# MB1137.net
KiCad netlist of a schematic drawn in Altium Designer
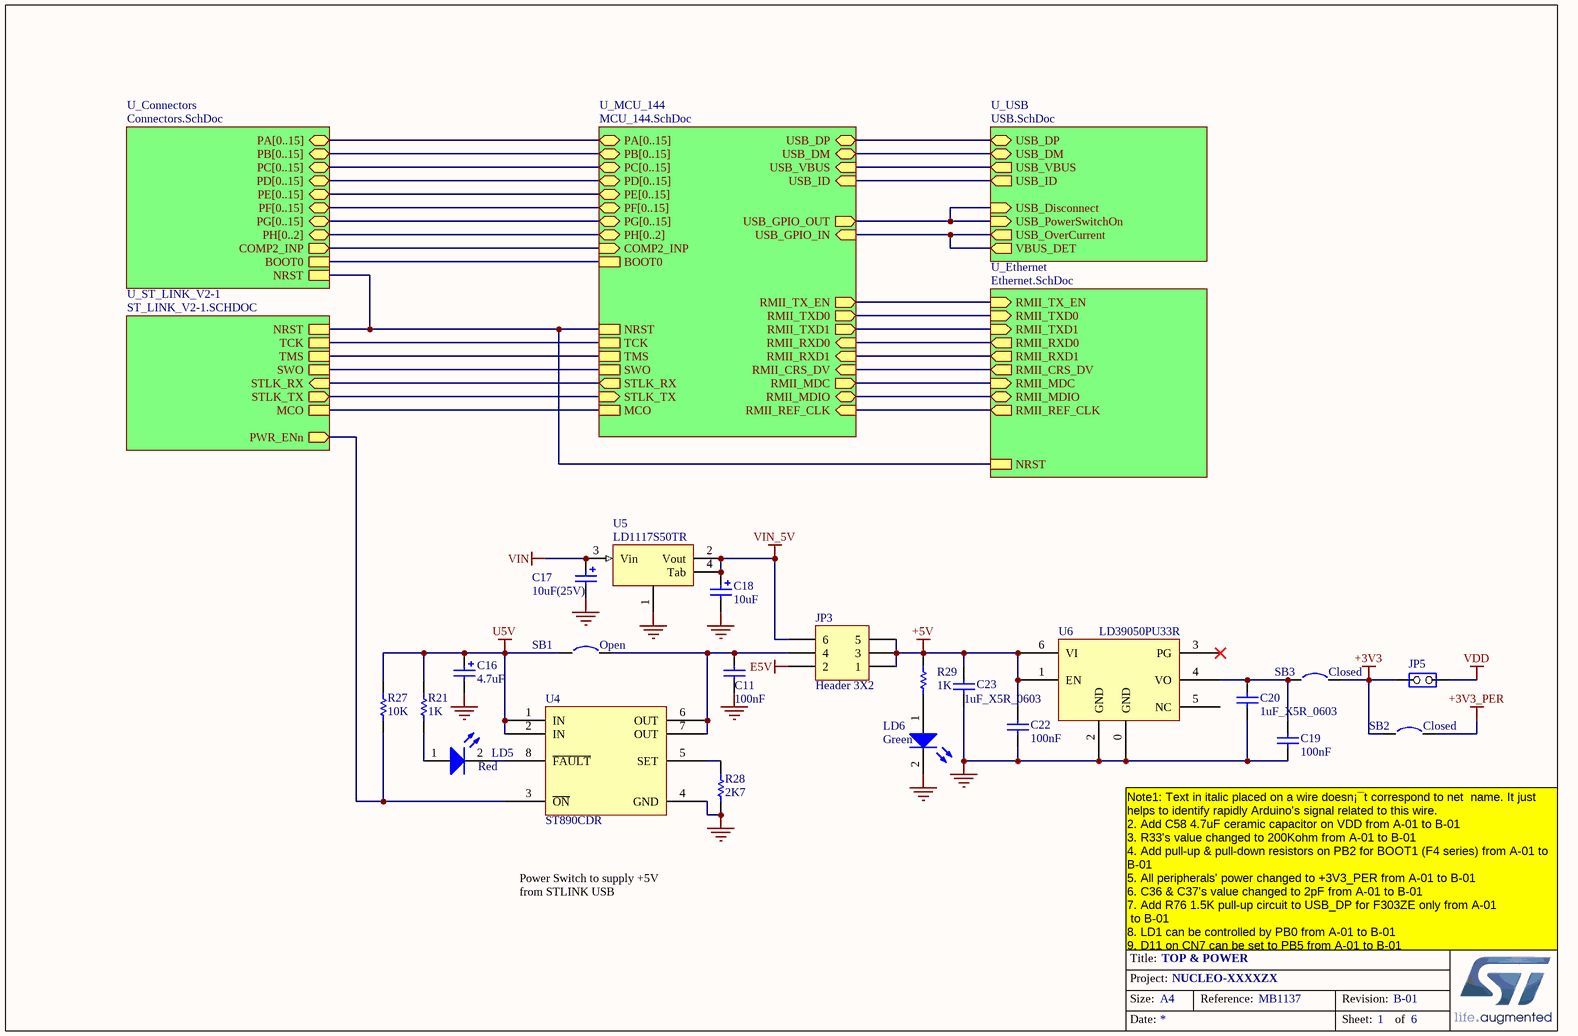
[diagram p0: MB1137.SchDoc]

(export (version "E")
  (design (tool "Eeschema 10.0.6"))
  (components
    (comp (ref "C11")
      (value "100nF")
      (footprint "0603C")
      (description "Capacitor 0402 / 0603 / 0805")
      (libsource (lib "MCD_TOOLS") (part "Capacitor_ST"))
    )
    (comp (ref "C16")
      (value "4.7uF")
      (footprint "TAN-A")
      (description "Polarized Capacitor (Radial)")
      (fields (field (name "PUBLISHER") "Altium Limited"))
      (libsource (lib "*") (part "Cap Pol1"))
    )
    (comp (ref "C17")
      (value "10uF(25V)")
      (footprint "TAN-B")
      (description "Polarized Capacitor (Radial)")
      (fields (field (name "PUBLISHER") "Altium Limited"))
      (libsource (lib "Miscellaneous Devices") (part "Cap Pol1"))
    )
    (comp (ref "C18")
      (value "10uF")
      (footprint "TAN-A")
      (description "Polarized Capacitor (Radial)")
      (fields (field (name "PUBLISHER") "Altium Limited"))
      (libsource (lib "Miscellaneous Devices") (part "Cap Pol1"))
    )
    (comp (ref "C19")
      (value "100nF")
      (footprint "0603C")
      (description "Capacitor 0402 / 0603 / 0805")
      (libsource (lib "MCD_TOOLS") (part "Capacitor_ST"))
    )
    (comp (ref "C20")
      (value "1uF_X5R_0603")
      (footprint "0603C")
      (description "0603  X5R 1µF")
      (fields (field (name "TOLERANCE") "10%"))
      (libsource (lib "MB963_1") (part "CAP SMD 0603  X5R 1µF 25V 10%"))
    )
    (comp (ref "C22")
      (value "100nF")
      (footprint "0603C")
      (description "Capacitor 0402 / 0603 / 0805")
      (libsource (lib "MCD_TOOLS") (part "Capacitor_ST"))
    )
    (comp (ref "C23")
      (value "1uF_X5R_0603")
      (footprint "0603C")
      (description "0603  X5R 1µF")
      (fields (field (name "TOLERANCE") "10%"))
      (libsource (lib "MB963_1") (part "CAP SMD 0603  X5R 1µF 25V 10%"))
    )
    (comp (ref "JP3")
      (value "Header 3X2")
      (footprint "HDR_3x2_2R54_V_M")
      (description "Header, 3-Pin, Dual row")
      (fields (field (name "PUBLISHER") "Altium Limited"))
      (libsource (lib "Miscellaneous Connectors") (part "Header 3X2"))
    )
    (comp (ref "JP5") (value "~") (footprint "HDR_1x2_2R54_V_M_S") (libsource (lib "*") (part "JP2")))
    (comp (ref "LD5")
      (value "Red")
      (footprint "0603D-R")
      (description "Typical RED, GREEN, YELLOW, AMBER GaAs LED")
      (fields (field (name "PUBLISHER") "Altium Limited"))
      (libsource (lib "Miscellaneous Devices") (part "LED2"))
    )
    (comp (ref "LD6")
      (value "Green")
      (footprint "0603D-G")
      (description "Typical RED, GREEN, YELLOW, AMBER GaAs LED")
      (fields (field (name "PUBLISHER") "Altium Limited"))
      (libsource (lib "") (part "LED2_1"))
    )
    (comp (ref "R21")
      (value "1K")
      (footprint "0603R")
      (description "Resistor")
      (fields (field (name "PUBLISHER") "Altium Limited"))
      (libsource (lib "*") (part "Res1"))
    )
    (comp (ref "R27")
      (value "10K")
      (footprint "STM-SMEE:0603R")
      (description "Resistor 0402 or 0603 or 0805")
      (libsource (lib "MCD_TOOLS") (part "Resistor_ST"))
    )
    (comp (ref "R28")
      (value "2K7")
      (footprint "STM-SMEE:0603R")
      (description "Resistor 0402 or 0603 or 0805")
      (libsource (lib "MCD_TOOLS") (part "Resistor_ST"))
    )
    (comp (ref "R29")
      (value "1K")
      (footprint "0603R")
      (description "Resistor 0402 or 0603 or 0805")
      (libsource (lib "MCD_TOOLS") (part "Resistor_ST"))
    )
    (comp (ref "SB1")
      (value "Open")
      (footprint "SB_0603")
      (description "Circuit Breaker")
      (fields (field (name "PUBLISHER") "Altium Limited"))
      (libsource (lib "MB1167") (part "Circuit Breaker"))
    )
    (comp (ref "SB2")
      (value "Closed")
      (footprint "SB_0603")
      (description "Circuit Breaker")
      (fields (field (name "PUBLISHER") "Altium Limited"))
      (libsource (lib "MB1167") (part "Circuit Breaker_close"))
    )
    (comp (ref "SB3")
      (value "Closed")
      (footprint "SB_0603")
      (description "Circuit Breaker")
      (fields (field (name "PUBLISHER") "Altium Limited"))
      (libsource (lib "MB1167") (part "Circuit Breaker_close"))
    )
    (comp (ref "U4")
      (value "ST890CDR")
      (footprint "SOIC8_1R27_4R9X6")
      (libsource (lib "MB1137") (part "ST890CDR"))
    )
    (comp (ref "U5") (value "LD1117S50TR") (footprint "SOT-223") (libsource (lib "MB1137") (part "LD1117")))
    (comp (ref "U6")
      (value "LD39050PU33R")
      (footprint "DFN6_0R95_3x3_TP")
      (libsource (lib "MB1137") (part "LD39050P"))
    )
  )
  (nets
    (net (code "1") (name "+3V3") (class "Default")
      (node (ref "JP5") (pin "1") (pinfunction "COMMON_1") (pintype "passive"))
      (node (ref "SB2") (pin "1") (pinfunction "1_1") (pintype "passive"))
      (node (ref "SB3") (pin "2") (pinfunction "2_2") (pintype "passive"))
    )
    (net (code "2") (name "+3V3_PER") (class "Default")
      (node (ref "SB2") (pin "2") (pinfunction "2_2") (pintype "passive"))
    )
    (net (code "3") (name "+5V") (class "Default")
      (node (ref "C22") (pin "2") (pinfunction "2_2") (pintype "passive"))
      (node (ref "C23") (pin "1") (pinfunction "1_1") (pintype "passive"))
      (node (ref "JP3") (pin "1") (pinfunction "1_1") (pintype "passive"))
      (node (ref "JP3") (pin "3") (pinfunction "3_3") (pintype "passive"))
      (node (ref "JP3") (pin "5") (pinfunction "5_5") (pintype "passive"))
      (node (ref "R29") (pin "2") (pinfunction "2_2") (pintype "passive"))
      (node (ref "U6") (pin "1") (pinfunction "EN_1") (pintype "passive"))
      (node (ref "U6") (pin "6") (pinfunction "VI_6") (pintype "passive"))
    )
    (net (code "16") (name "/PWR_ENn") (class "Default")
      (node (ref "R27") (pin "2") (pinfunction "2_2") (pintype "passive"))
      (node (ref "U4") (pin "3") (pinfunction "~{ON}_3") (pintype "passive"))
    )
    (net (code "37") (name "E5V") (class "Default")
      (node (ref "JP3") (pin "2") (pinfunction "2_2") (pintype "passive"))
    )
    (net (code "38") (name "GND") (class "Default")
      (node (ref "C11") (pin "1") (pinfunction "1_1") (pintype "passive"))
      (node (ref "C16") (pin "2") (pinfunction "2_2") (pintype "passive"))
      (node (ref "C17") (pin "2") (pinfunction "2_2") (pintype "passive"))
      (node (ref "C18") (pin "2") (pinfunction "2_2") (pintype "passive"))
      (node (ref "C19") (pin "1") (pinfunction "1_1") (pintype "passive"))
      (node (ref "C20") (pin "2") (pinfunction "2_2") (pintype "passive"))
      (node (ref "C22") (pin "1") (pinfunction "1_1") (pintype "passive"))
      (node (ref "C23") (pin "2") (pinfunction "2_2") (pintype "passive"))
      (node (ref "LD6") (pin "2") (pinfunction "K_2") (pintype "passive"))
      (node (ref "R28") (pin "1") (pinfunction "1_1") (pintype "passive"))
      (node (ref "U4") (pin "4") (pinfunction "GND_4") (pintype "passive"))
      (node (ref "U5") (pin "1") (pintype "passive"))
      (node (ref "U6") (pin "0") (pinfunction "GND_0") (pintype "passive"))
      (node (ref "U6") (pin "2") (pinfunction "GND_2") (pintype "passive"))
    )
    (net (code "39") (name "Net-(C11-Pad2)") (class "Default")
      (node (ref "C11") (pin "2") (pinfunction "2_2") (pintype "passive"))
      (node (ref "JP3") (pin "4") (pinfunction "4_4") (pintype "passive"))
      (node (ref "SB1") (pin "2") (pinfunction "2_2") (pintype "passive"))
      (node (ref "U4") (pin "6") (pinfunction "OUT_6") (pintype "passive"))
      (node (ref "U4") (pin "7") (pinfunction "OUT_7") (pintype "passive"))
    )
    (net (code "40") (name "Net-(LD5-A)") (class "Default")
      (node (ref "LD5") (pin "1") (pinfunction "A_1") (pintype "passive"))
      (node (ref "R21") (pin "2") (pinfunction "2_2") (pintype "passive"))
    )
    (net (code "41") (name "Net-(LD5-K)") (class "Default")
      (node (ref "LD5") (pin "2") (pinfunction "K_2") (pintype "passive"))
      (node (ref "U4") (pin "8") (pinfunction "~{FAULT}_8") (pintype "passive"))
    )
    (net (code "42") (name "Net-(LD6-A)") (class "Default")
      (node (ref "LD6") (pin "1") (pinfunction "A_1") (pintype "passive"))
      (node (ref "R29") (pin "1") (pinfunction "1_1") (pintype "passive"))
    )
    (net (code "43") (name "Net-(U4-SET)") (class "Default")
      (node (ref "R28") (pin "2") (pinfunction "2_2") (pintype "passive"))
      (node (ref "U4") (pin "5") (pinfunction "SET_5") (pintype "passive"))
    )
    (net (code "44") (name "Net-(U6-VO)") (class "Default")
      (node (ref "C19") (pin "2") (pinfunction "2_2") (pintype "passive"))
      (node (ref "C20") (pin "1") (pinfunction "1_1") (pintype "passive"))
      (node (ref "SB3") (pin "1") (pinfunction "1_1") (pintype "passive"))
      (node (ref "U6") (pin "4") (pinfunction "VO_4") (pintype "passive"))
    )
    (net (code "45") (name "U5V") (class "Default")
      (node (ref "C16") (pin "1") (pinfunction "1_1") (pintype "passive"))
      (node (ref "R21") (pin "1") (pinfunction "1_1") (pintype "passive"))
      (node (ref "R27") (pin "1") (pinfunction "1_1") (pintype "passive"))
      (node (ref "SB1") (pin "1") (pinfunction "1_1") (pintype "passive"))
      (node (ref "U4") (pin "1") (pinfunction "IN_1") (pintype "passive"))
      (node (ref "U4") (pin "2") (pinfunction "IN_2") (pintype "passive"))
    )
    (net (code "46") (name "VDD") (class "Default")
      (node (ref "JP5") (pin "2") (pinfunction "NO_2") (pintype "passive"))
    )
    (net (code "47") (name "VIN") (class "Default")
      (node (ref "C17") (pin "1") (pinfunction "1_1") (pintype "passive"))
      (node (ref "U5") (pin "3") (pinfunction "Vin_3") (pintype "input"))
    )
    (net (code "48") (name "VIN_5V") (class "Default")
      (node (ref "C18") (pin "1") (pinfunction "1_1") (pintype "passive"))
      (node (ref "JP3") (pin "6") (pinfunction "6_6") (pintype "passive"))
      (node (ref "U5") (pin "2") (pinfunction "Vout_2") (pintype "power_in"))
      (node (ref "U5") (pin "4") (pinfunction "Tab_4") (pintype "power_in"))
    )
    (net (code "49") (name "unconnected-(U6-NC-Pad5)") (class "Default")
      (node (ref "U6") (pin "5") (pinfunction "NC_5") (pintype "passive"))
    )
    (net (code "50") (name "unconnected-(U6-PG-Pad3)") (class "Default")
      (node (ref "U6") (pin "3") (pinfunction "PG_3") (pintype "passive+no_connect"))
    )
  )
)
